# MainBoard.net
KiCad netlist of a schematic drawn in EAGLE
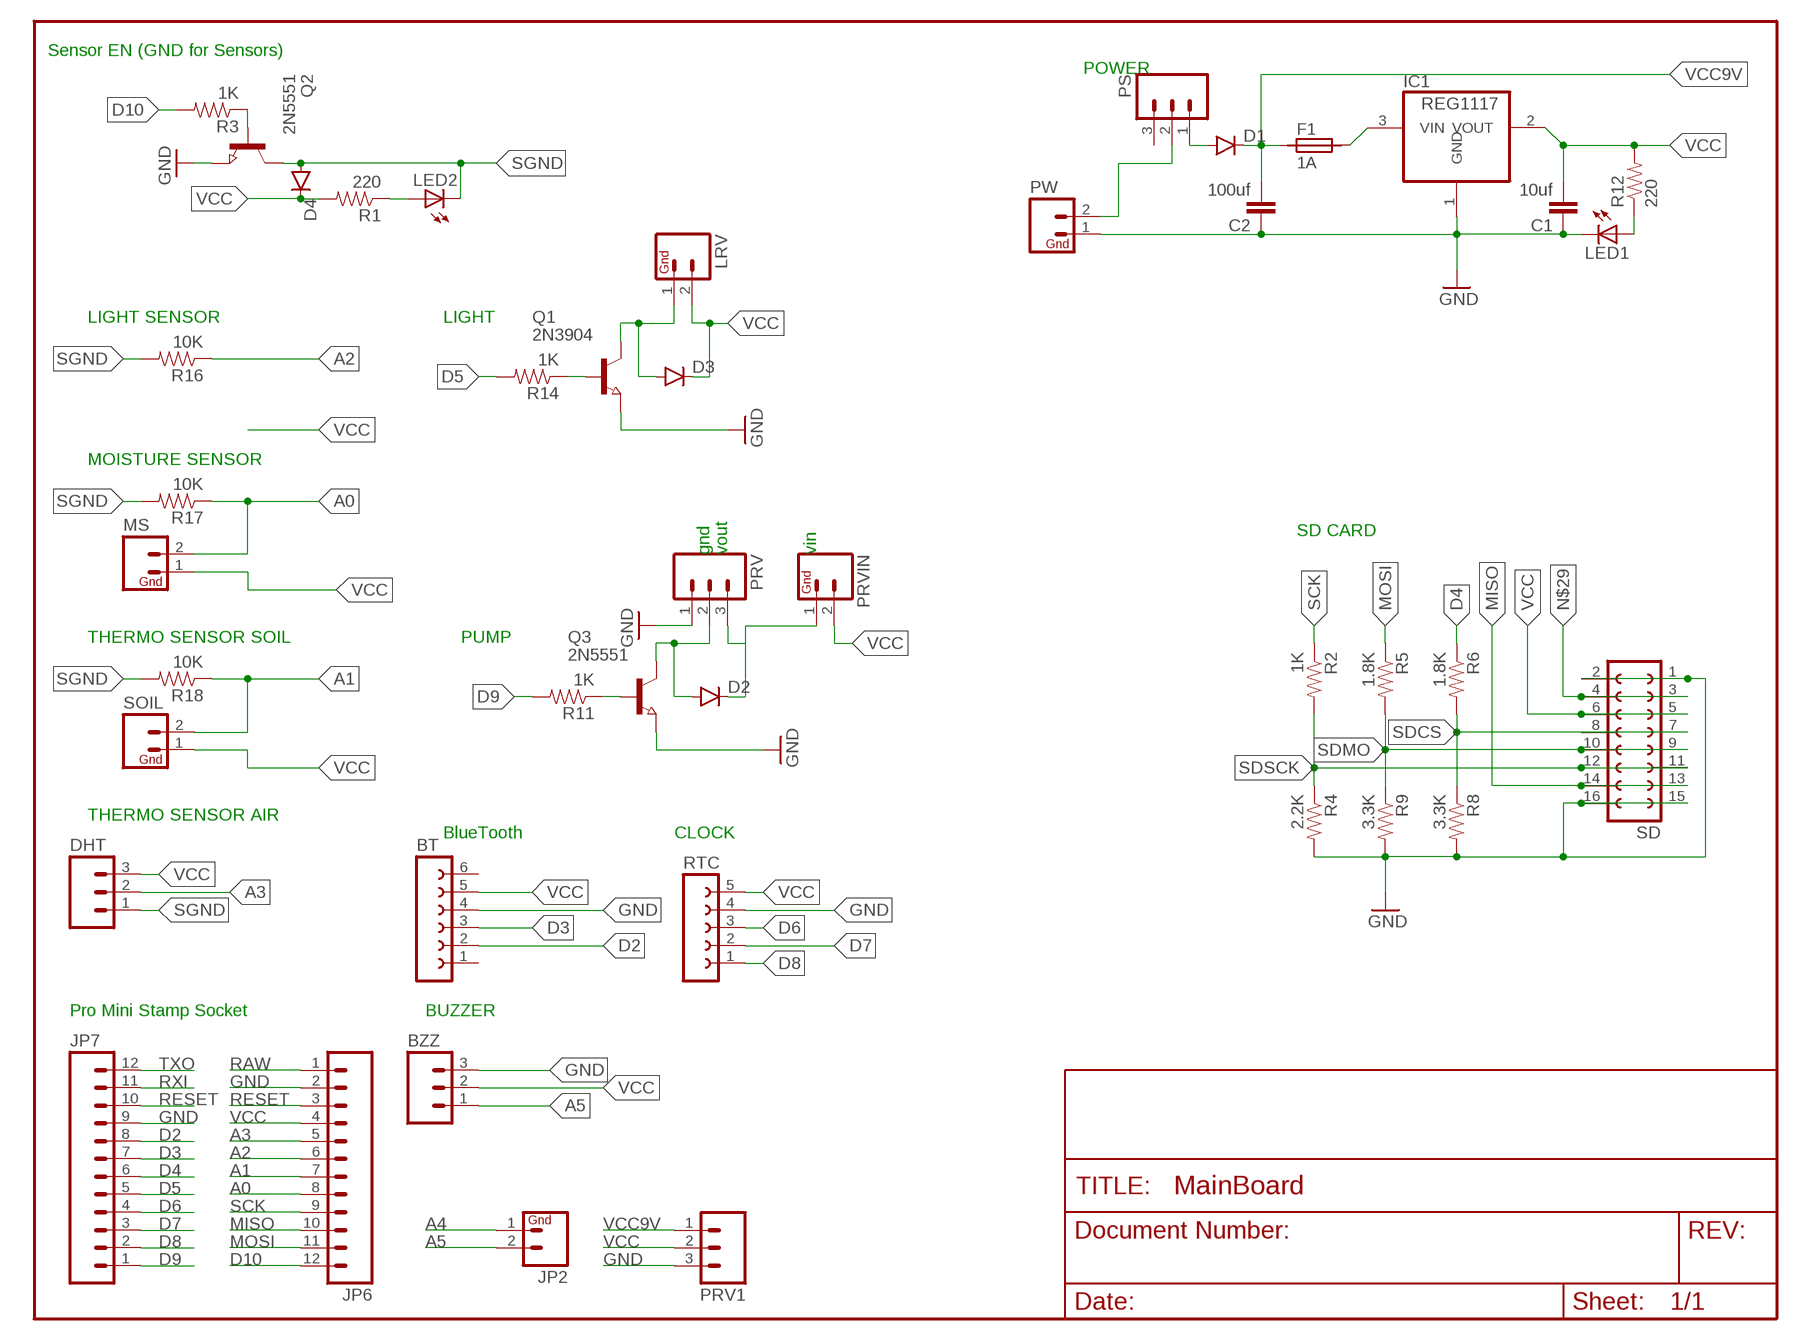
[diagram p0: schematic, sheet 1]

(export (version "E")
  (design (tool "Eeschema 10.0.6"))
  (components
    (comp (ref "BT")
      (value "FE06-1")
      (footprint "eagle-import:FE06")
      (libsource (lib "eagle-import") (part "FE06-1"))
    )
    (comp (ref "BZZ")
      (value "M03PTH")
      (footprint "eagle-import:1X03")
      (libsource (lib "eagle-import") (part "M03PTH"))
    )
    (comp (ref "C1")
      (value "10uf")
      (footprint "eagle-import:0805")
      (libsource (lib "eagle-import") (part "CAP0805"))
    )
    (comp (ref "C2")
      (value "100uf")
      (footprint "eagle-import:0805")
      (libsource (lib "eagle-import") (part "CAP0805"))
    )
    (comp (ref "D1")
      (value "DIODESMA")
      (footprint "eagle-import:SMA-DIODE")
      (libsource (lib "eagle-import") (part "DIODESMA"))
    )
    (comp (ref "D2")
      (value "DIODESMA")
      (footprint "eagle-import:SMA-DIODE")
      (libsource (lib "eagle-import") (part "DIODESMA"))
    )
    (comp (ref "D3")
      (value "DIODESMA")
      (footprint "eagle-import:SMA-DIODE")
      (libsource (lib "eagle-import") (part "DIODESMA"))
    )
    (comp (ref "D4")
      (value "DIODESMA")
      (footprint "eagle-import:SMA-DIODE")
      (libsource (lib "eagle-import") (part "DIODESMA"))
    )
    (comp (ref "DHT")
      (value "M03PTH")
      (footprint "eagle-import:1X03")
      (libsource (lib "eagle-import") (part "M03PTH"))
    )
    (comp (ref "F1")
      (value "1A")
      (footprint "eagle-import:1820")
      (libsource (lib "eagle-import") (part "SIBA194600"))
    )
    (comp (ref "IC1")
      (value "REG1117")
      (footprint "eagle-import:SOT223")
      (libsource (lib "eagle-import") (part "REG1117"))
    )
    (comp (ref "JP2")
      (value "M02PTH")
      (footprint "eagle-import:1X02")
      (libsource (lib "eagle-import") (part "M02PTH"))
    )
    (comp (ref "JP6")
      (value "M12PTH")
      (footprint "eagle-import:1X12")
      (libsource (lib "eagle-import") (part "M12PTH"))
    )
    (comp (ref "JP7")
      (value "M12PTH")
      (footprint "eagle-import:1X12")
      (libsource (lib "eagle-import") (part "M12PTH"))
    )
    (comp (ref "LED1")
      (value "LEDCHIP-LED0805")
      (footprint "eagle-import:CHIP-LED0805")
      (libsource (lib "eagle-import") (part "LEDCHIP-LED0805"))
    )
    (comp (ref "LED2")
      (value "LEDCHIP-LED0805")
      (footprint "eagle-import:CHIP-LED0805")
      (libsource (lib "eagle-import") (part "LEDCHIP-LED0805"))
    )
    (comp (ref "LRV")
      (value "M02PTH")
      (footprint "eagle-import:1X02")
      (libsource (lib "eagle-import") (part "M02PTH"))
    )
    (comp (ref "MS")
      (value "M02PTH")
      (footprint "eagle-import:1X02")
      (libsource (lib "eagle-import") (part "M02PTH"))
    )
    (comp (ref "PRV")
      (value "M03PTH")
      (footprint "eagle-import:1X03")
      (libsource (lib "eagle-import") (part "M03PTH"))
    )
    (comp (ref "PRV1")
      (value "M03PTH")
      (footprint "eagle-import:1X03")
      (libsource (lib "eagle-import") (part "M03PTH"))
    )
    (comp (ref "PRVIN")
      (value "M02PTH")
      (footprint "eagle-import:1X02")
      (libsource (lib "eagle-import") (part "M02PTH"))
    )
    (comp (ref "PS")
      (value "M03PTH")
      (footprint "eagle-import:1X03")
      (libsource (lib "eagle-import") (part "M03PTH"))
    )
    (comp (ref "PW")
      (value "M02PTH")
      (footprint "eagle-import:1X02")
      (libsource (lib "eagle-import") (part "M02PTH"))
    )
    (comp (ref "Q1")
      (value "2N3904")
      (footprint "eagle-import:SOT23")
      (libsource (lib "eagle-import") (part "NPN-TRANSISTOR_SOT23"))
    )
    (comp (ref "Q2")
      (value "2N5551")
      (footprint "eagle-import:SOT23")
      (libsource (lib "eagle-import") (part "NPN-TRANSISTOR_SOT23"))
    )
    (comp (ref "Q3")
      (value "2N5551")
      (footprint "eagle-import:SOT23")
      (libsource (lib "eagle-import") (part "NPN-TRANSISTOR_SOT23"))
    )
    (comp (ref "R1")
      (value "220")
      (footprint "eagle-import:0805")
      (libsource (lib "eagle-import") (part "RESISTOR0805-RES"))
    )
    (comp (ref "R2")
      (value "1K")
      (footprint "eagle-import:0805")
      (libsource (lib "eagle-import") (part "RESISTOR0805-RES"))
    )
    (comp (ref "R3")
      (value "1K")
      (footprint "eagle-import:0805")
      (libsource (lib "eagle-import") (part "RESISTOR0805-RES"))
    )
    (comp (ref "R4")
      (value "2.2K")
      (footprint "eagle-import:0805")
      (libsource (lib "eagle-import") (part "RESISTOR0805-RES"))
    )
    (comp (ref "R5")
      (value "1.8K")
      (footprint "eagle-import:0805")
      (libsource (lib "eagle-import") (part "RESISTOR0805-RES"))
    )
    (comp (ref "R6")
      (value "1.8K")
      (footprint "eagle-import:0805")
      (libsource (lib "eagle-import") (part "RESISTOR0805-RES"))
    )
    (comp (ref "R8")
      (value "3.3K")
      (footprint "eagle-import:0805")
      (libsource (lib "eagle-import") (part "RESISTOR0805-RES"))
    )
    (comp (ref "R9")
      (value "3.3K")
      (footprint "eagle-import:0805")
      (libsource (lib "eagle-import") (part "RESISTOR0805-RES"))
    )
    (comp (ref "R11")
      (value "1K")
      (footprint "eagle-import:0805")
      (libsource (lib "eagle-import") (part "RESISTOR0805-RES"))
    )
    (comp (ref "R12")
      (value "220")
      (footprint "eagle-import:0805")
      (libsource (lib "eagle-import") (part "RESISTOR0805-RES"))
    )
    (comp (ref "R14")
      (value "1K")
      (footprint "eagle-import:0805")
      (libsource (lib "eagle-import") (part "RESISTOR0805-RES"))
    )
    (comp (ref "R16")
      (value "10K")
      (footprint "eagle-import:0805")
      (libsource (lib "eagle-import") (part "RESISTOR0805-RES"))
    )
    (comp (ref "R17")
      (value "10K")
      (footprint "eagle-import:0805")
      (libsource (lib "eagle-import") (part "RESISTOR0805-RES"))
    )
    (comp (ref "R18")
      (value "10K")
      (footprint "eagle-import:0805")
      (libsource (lib "eagle-import") (part "RESISTOR0805-RES"))
    )
    (comp (ref "RTC")
      (value "FE05-1")
      (footprint "eagle-import:FE05-1")
      (libsource (lib "eagle-import") (part "FE05-1"))
    )
    (comp (ref "SD")
      (value "FE08-2")
      (footprint "eagle-import:FE08-2")
      (libsource (lib "eagle-import") (part "FE08-2"))
    )
    (comp (ref "SOIL")
      (value "M02PTH")
      (footprint "eagle-import:1X02")
      (libsource (lib "eagle-import") (part "M02PTH"))
    )
  )
  (nets
    (net (code "1") (name "/A4") (class "Default")
      (node (ref "JP2") (pin "1") (pinfunction "1_1") (pintype "passive"))
    )
    (net (code "2") (name "/RAW") (class "Default")
      (node (ref "JP6") (pin "1") (pinfunction "1_1") (pintype "passive"))
    )
    (net (code "3") (name "/RESET") (class "Default")
      (node (ref "JP6") (pin "3") (pinfunction "3_3") (pintype "passive"))
      (node (ref "JP7") (pin "10") (pinfunction "10_10") (pintype "passive"))
    )
    (net (code "4") (name "/RXI") (class "Default")
      (node (ref "JP7") (pin "11") (pinfunction "11_11") (pintype "passive"))
    )
    (net (code "5") (name "/TXO") (class "Default")
      (node (ref "JP7") (pin "12") (pinfunction "12_12") (pintype "passive"))
    )
    (net (code "6") (name "A0") (class "Default")
      (node (ref "JP6") (pin "8") (pinfunction "8_8") (pintype "passive"))
      (node (ref "MS") (pin "2") (pinfunction "2_2") (pintype "passive"))
      (node (ref "R17") (pin "1") (pinfunction "1_1") (pintype "passive"))
    )
    (net (code "7") (name "A1") (class "Default")
      (node (ref "JP6") (pin "7") (pinfunction "7_7") (pintype "passive"))
      (node (ref "R18") (pin "1") (pinfunction "1_1") (pintype "passive"))
      (node (ref "SOIL") (pin "2") (pinfunction "2_2") (pintype "passive"))
    )
    (net (code "8") (name "A2") (class "Default")
      (node (ref "JP6") (pin "6") (pinfunction "6_6") (pintype "passive"))
      (node (ref "R16") (pin "1") (pinfunction "1_1") (pintype "passive"))
    )
    (net (code "9") (name "A3") (class "Default")
      (node (ref "DHT") (pin "2") (pinfunction "2_2") (pintype "passive"))
      (node (ref "JP6") (pin "5") (pinfunction "5_5") (pintype "passive"))
    )
    (net (code "10") (name "A5") (class "Default")
      (node (ref "BZZ") (pin "1") (pinfunction "1_1") (pintype "passive"))
      (node (ref "JP2") (pin "2") (pinfunction "2_2") (pintype "passive"))
    )
    (net (code "11") (name "D2") (class "Default")
      (node (ref "BT") (pin "2") (pinfunction "2_2") (pintype "passive"))
      (node (ref "JP7") (pin "8") (pinfunction "8_8") (pintype "passive"))
    )
    (net (code "12") (name "D3") (class "Default")
      (node (ref "BT") (pin "3") (pinfunction "3_3") (pintype "passive"))
      (node (ref "JP7") (pin "7") (pinfunction "7_7") (pintype "passive"))
    )
    (net (code "13") (name "D4") (class "Default")
      (node (ref "JP7") (pin "6") (pinfunction "6_6") (pintype "passive"))
      (node (ref "R6") (pin "1") (pinfunction "1_1") (pintype "passive"))
    )
    (net (code "14") (name "D5") (class "Default")
      (node (ref "JP7") (pin "5") (pinfunction "5_5") (pintype "passive"))
      (node (ref "R14") (pin "2") (pinfunction "2_2") (pintype "passive"))
    )
    (net (code "15") (name "D6") (class "Default")
      (node (ref "JP7") (pin "4") (pinfunction "4_4") (pintype "passive"))
      (node (ref "RTC") (pin "3") (pinfunction "3_3") (pintype "passive"))
    )
    (net (code "16") (name "D7") (class "Default")
      (node (ref "JP7") (pin "3") (pinfunction "3_3") (pintype "passive"))
      (node (ref "RTC") (pin "2") (pinfunction "2_2") (pintype "passive"))
    )
    (net (code "17") (name "D8") (class "Default")
      (node (ref "JP7") (pin "2") (pinfunction "2_2") (pintype "passive"))
      (node (ref "RTC") (pin "1") (pinfunction "1_1") (pintype "passive"))
    )
    (net (code "18") (name "D9") (class "Default")
      (node (ref "JP7") (pin "1") (pinfunction "1_1") (pintype "passive"))
      (node (ref "R11") (pin "2") (pinfunction "2_2") (pintype "passive"))
    )
    (net (code "19") (name "D10") (class "Default")
      (node (ref "JP6") (pin "12") (pinfunction "12_12") (pintype "passive"))
      (node (ref "R3") (pin "2") (pinfunction "2_2") (pintype "passive"))
    )
    (net (code "20") (name "GND") (class "Default")
      (node (ref "BT") (pin "4") (pinfunction "4_4") (pintype "passive"))
      (node (ref "BZZ") (pin "3") (pinfunction "3_3") (pintype "passive"))
      (node (ref "C1") (pin "1") (pinfunction "1_1") (pintype "passive"))
      (node (ref "C2") (pin "1") (pinfunction "1_1") (pintype "passive"))
      (node (ref "IC1") (pin "1") (pinfunction "GND_1") (pintype "power_in"))
      (node (ref "JP6") (pin "2") (pinfunction "2_2") (pintype "passive"))
      (node (ref "JP7") (pin "9") (pinfunction "9_9") (pintype "passive"))
      (node (ref "LED1") (pin "C") (pinfunction "C_C") (pintype "passive"))
      (node (ref "PRV") (pin "1") (pinfunction "1_1") (pintype "passive"))
      (node (ref "PRV1") (pin "3") (pinfunction "3_3") (pintype "passive"))
      (node (ref "PW") (pin "1") (pinfunction "1_1") (pintype "passive"))
      (node (ref "Q1") (pin "2") (pinfunction "E_2") (pintype "passive"))
      (node (ref "Q2") (pin "2") (pinfunction "E_2") (pintype "passive"))
      (node (ref "Q3") (pin "2") (pinfunction "E_2") (pintype "passive"))
      (node (ref "R4") (pin "2") (pinfunction "2_2") (pintype "passive"))
      (node (ref "R8") (pin "2") (pinfunction "2_2") (pintype "passive"))
      (node (ref "R9") (pin "2") (pinfunction "2_2") (pintype "passive"))
      (node (ref "RTC") (pin "4") (pinfunction "4_4") (pintype "passive"))
      (node (ref "SD") (pin "1") (pinfunction "1_1") (pintype "passive"))
      (node (ref "SD") (pin "15") (pinfunction "15_15") (pintype "passive"))
      (node (ref "SD") (pin "16") (pinfunction "16_16") (pintype "passive"))
      (node (ref "SD") (pin "2") (pinfunction "2_2") (pintype "passive"))
    )
    (net (code "21") (name "MISO") (class "Default")
      (node (ref "JP6") (pin "10") (pinfunction "10_10") (pintype "passive"))
      (node (ref "SD") (pin "13") (pinfunction "13_13") (pintype "passive"))
      (node (ref "SD") (pin "14") (pinfunction "14_14") (pintype "passive"))
    )
    (net (code "22") (name "MOSI") (class "Default")
      (node (ref "JP6") (pin "11") (pinfunction "11_11") (pintype "passive"))
      (node (ref "R5") (pin "1") (pinfunction "1_1") (pintype "passive"))
    )
    (net (code "23") (name "N$29") (class "Default")
      (node (ref "SD") (pin "3") (pinfunction "3_3") (pintype "passive"))
      (node (ref "SD") (pin "4") (pinfunction "4_4") (pintype "passive"))
    )
    (net (code "24") (name "Net-(D1-PadA)") (class "Default")
      (node (ref "D1") (pin "A") (pinfunction "A_A") (pintype "passive"))
      (node (ref "PS") (pin "1") (pinfunction "1_1") (pintype "passive"))
    )
    (net (code "25") (name "Net-(D2-PadC)") (class "Default")
      (node (ref "D2") (pin "C") (pinfunction "C_C") (pintype "passive"))
      (node (ref "PRV") (pin "3") (pinfunction "3_3") (pintype "passive"))
      (node (ref "PRVIN") (pin "1") (pinfunction "1_1") (pintype "passive"))
    )
    (net (code "26") (name "Net-(IC1-VIN)") (class "Default")
      (node (ref "F1") (pin "2") (pinfunction "2_2") (pintype "passive"))
      (node (ref "IC1") (pin "3") (pinfunction "VIN_3") (pintype "input"))
    )
    (net (code "27") (name "Net-(LED1-PadA)") (class "Default")
      (node (ref "LED1") (pin "A") (pinfunction "A_A") (pintype "passive"))
      (node (ref "R12") (pin "1") (pinfunction "1_1") (pintype "passive"))
    )
    (net (code "28") (name "Net-(LED2-PadA)") (class "Default")
      (node (ref "LED2") (pin "A") (pinfunction "A_A") (pintype "passive"))
      (node (ref "R1") (pin "1") (pinfunction "1_1") (pintype "passive"))
    )
    (net (code "29") (name "Net-(PS-Pad2)") (class "Default")
      (node (ref "PS") (pin "2") (pinfunction "2_2") (pintype "passive"))
      (node (ref "PW") (pin "2") (pinfunction "2_2") (pintype "passive"))
    )
    (net (code "30") (name "Net-(Q1-B)") (class "Default")
      (node (ref "Q1") (pin "1") (pinfunction "B_1") (pintype "passive"))
      (node (ref "R14") (pin "1") (pinfunction "1_1") (pintype "passive"))
    )
    (net (code "31") (name "Net-(Q1-C)") (class "Default")
      (node (ref "D3") (pin "A") (pinfunction "A_A") (pintype "passive"))
      (node (ref "LRV") (pin "1") (pinfunction "1_1") (pintype "passive"))
      (node (ref "Q1") (pin "3") (pinfunction "C_3") (pintype "passive"))
    )
    (net (code "32") (name "Net-(Q2-B)") (class "Default")
      (node (ref "Q2") (pin "1") (pinfunction "B_1") (pintype "passive"))
      (node (ref "R3") (pin "1") (pinfunction "1_1") (pintype "passive"))
    )
    (net (code "33") (name "Net-(Q3-B)") (class "Default")
      (node (ref "Q3") (pin "1") (pinfunction "B_1") (pintype "passive"))
      (node (ref "R11") (pin "1") (pinfunction "1_1") (pintype "passive"))
    )
    (net (code "34") (name "Net-(Q3-C)") (class "Default")
      (node (ref "D2") (pin "A") (pinfunction "A_A") (pintype "passive"))
      (node (ref "PRV") (pin "2") (pinfunction "2_2") (pintype "passive"))
      (node (ref "Q3") (pin "3") (pinfunction "C_3") (pintype "passive"))
    )
    (net (code "35") (name "SCK") (class "Default")
      (node (ref "JP6") (pin "9") (pinfunction "9_9") (pintype "passive"))
      (node (ref "R2") (pin "1") (pinfunction "1_1") (pintype "passive"))
    )
    (net (code "36") (name "SDCS") (class "Default")
      (node (ref "R6") (pin "2") (pinfunction "2_2") (pintype "passive"))
      (node (ref "R8") (pin "1") (pinfunction "1_1") (pintype "passive"))
      (node (ref "SD") (pin "7") (pinfunction "7_7") (pintype "passive"))
      (node (ref "SD") (pin "8") (pinfunction "8_8") (pintype "passive"))
    )
    (net (code "37") (name "SDMO") (class "Default")
      (node (ref "R5") (pin "2") (pinfunction "2_2") (pintype "passive"))
      (node (ref "R9") (pin "1") (pinfunction "1_1") (pintype "passive"))
      (node (ref "SD") (pin "10") (pinfunction "10_10") (pintype "passive"))
      (node (ref "SD") (pin "9") (pinfunction "9_9") (pintype "passive"))
    )
    (net (code "38") (name "SDSCK") (class "Default")
      (node (ref "R2") (pin "2") (pinfunction "2_2") (pintype "passive"))
      (node (ref "R4") (pin "1") (pinfunction "1_1") (pintype "passive"))
      (node (ref "SD") (pin "11") (pinfunction "11_11") (pintype "passive"))
      (node (ref "SD") (pin "12") (pinfunction "12_12") (pintype "passive"))
    )
    (net (code "39") (name "SGND") (class "Default")
      (node (ref "D4") (pin "A") (pinfunction "A_A") (pintype "passive"))
      (node (ref "DHT") (pin "1") (pinfunction "1_1") (pintype "passive"))
      (node (ref "LED2") (pin "C") (pinfunction "C_C") (pintype "passive"))
      (node (ref "Q2") (pin "3") (pinfunction "C_3") (pintype "passive"))
      (node (ref "R16") (pin "2") (pinfunction "2_2") (pintype "passive"))
      (node (ref "R17") (pin "2") (pinfunction "2_2") (pintype "passive"))
      (node (ref "R18") (pin "2") (pinfunction "2_2") (pintype "passive"))
    )
    (net (code "40") (name "VCC") (class "Default")
      (node (ref "BT") (pin "5") (pinfunction "5_5") (pintype "passive"))
      (node (ref "BZZ") (pin "2") (pinfunction "2_2") (pintype "passive"))
      (node (ref "C1") (pin "2") (pinfunction "2_2") (pintype "passive"))
      (node (ref "D3") (pin "C") (pinfunction "C_C") (pintype "passive"))
      (node (ref "D4") (pin "C") (pinfunction "C_C") (pintype "passive"))
      (node (ref "DHT") (pin "3") (pinfunction "3_3") (pintype "passive"))
      (node (ref "IC1") (pin "2") (pinfunction "VOUT_2") (pintype "output"))
      (node (ref "JP6") (pin "4") (pinfunction "4_4") (pintype "passive"))
      (node (ref "LRV") (pin "2") (pinfunction "2_2") (pintype "passive"))
      (node (ref "MS") (pin "1") (pinfunction "1_1") (pintype "passive"))
      (node (ref "PRV1") (pin "2") (pinfunction "2_2") (pintype "passive"))
      (node (ref "PRVIN") (pin "2") (pinfunction "2_2") (pintype "passive"))
      (node (ref "R1") (pin "2") (pinfunction "2_2") (pintype "passive"))
      (node (ref "R12") (pin "2") (pinfunction "2_2") (pintype "passive"))
      (node (ref "RTC") (pin "5") (pinfunction "5_5") (pintype "passive"))
      (node (ref "SD") (pin "5") (pinfunction "5_5") (pintype "passive"))
      (node (ref "SD") (pin "6") (pinfunction "6_6") (pintype "passive"))
      (node (ref "SOIL") (pin "1") (pinfunction "1_1") (pintype "passive"))
    )
    (net (code "41") (name "VCC9V") (class "Default")
      (node (ref "C2") (pin "2") (pinfunction "2_2") (pintype "passive"))
      (node (ref "D1") (pin "C") (pinfunction "C_C") (pintype "passive"))
      (node (ref "F1") (pin "1") (pinfunction "1_1") (pintype "passive"))
      (node (ref "PRV1") (pin "1") (pinfunction "1_1") (pintype "passive"))
    )
    (net (code "42") (name "unconnected-(BT-Pad1)") (class "Default")
      (node (ref "BT") (pin "1") (pinfunction "1_1") (pintype "passive"))
    )
    (net (code "43") (name "unconnected-(BT-Pad6)") (class "Default")
      (node (ref "BT") (pin "6") (pinfunction "6_6") (pintype "passive"))
    )
    (net (code "44") (name "unconnected-(PS-Pad3)") (class "Default")
      (node (ref "PS") (pin "3") (pinfunction "3_3") (pintype "passive"))
    )
  )
)
